# gen2down6basic.net
KiCad netlist of a schematic drawn in EAGLE
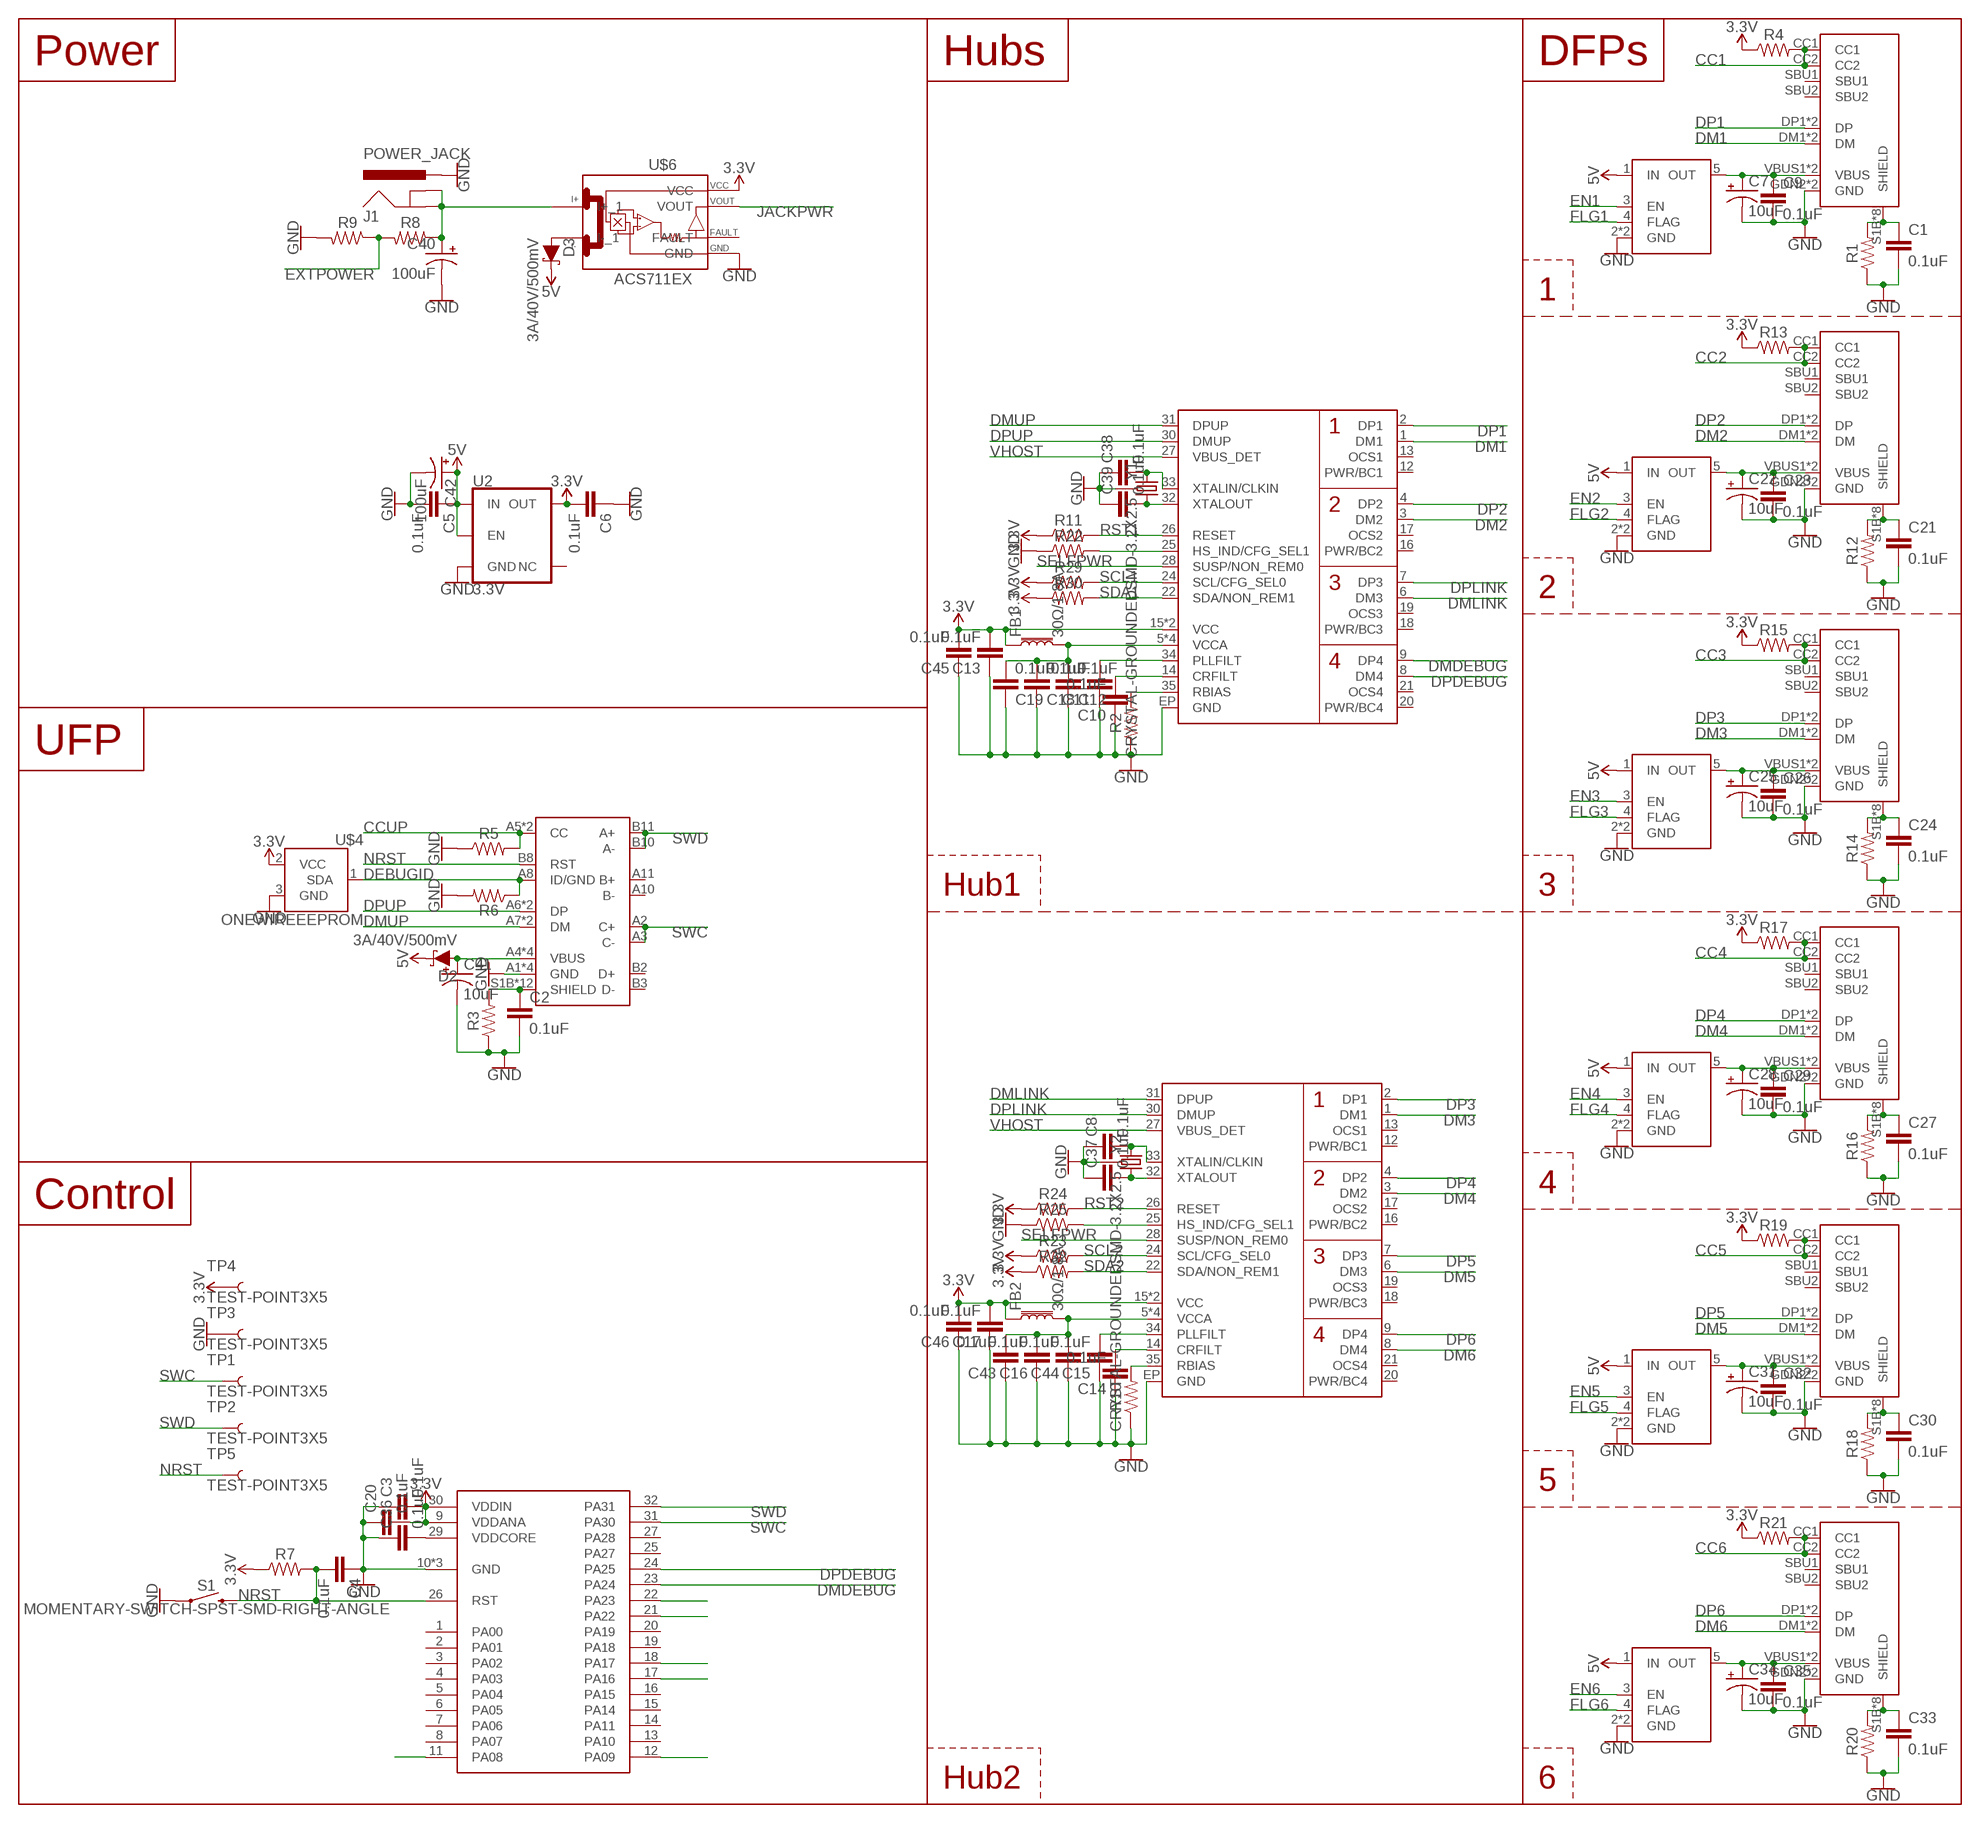
[diagram p0: schematic, sheet 1]

(export (version "E")
  (design (tool "Eeschema 10.0.6"))
  (components
    (comp (ref "C1")
      (value "0.1uF")
      (footprint "eagle-import:0603")
      (libsource (lib "eagle-import") (part "0.1UF-0603-25V-(+80/-20%)"))
    )
    (comp (ref "C2")
      (value "0.1uF")
      (footprint "eagle-import:0603")
      (libsource (lib "eagle-import") (part "0.1UF-0603-25V-(+80/-20%)"))
    )
    (comp (ref "C3")
      (value "0.1uF")
      (footprint "eagle-import:0603")
      (libsource (lib "eagle-import") (part "0.1UF-0603-25V-(+80/-20%)"))
    )
    (comp (ref "C4")
      (value "0.1uF")
      (footprint "eagle-import:0603")
      (libsource (lib "eagle-import") (part "0.1UF-0603-25V-(+80/-20%)"))
    )
    (comp (ref "C5")
      (value "0.1uF")
      (footprint "eagle-import:0603")
      (libsource (lib "eagle-import") (part "0.1UF-0603-25V-(+80/-20%)"))
    )
    (comp (ref "C6")
      (value "0.1uF")
      (footprint "eagle-import:0603")
      (libsource (lib "eagle-import") (part "0.1UF-0603-25V-(+80/-20%)"))
    )
    (comp (ref "C7")
      (value "10uF")
      (footprint "eagle-import:CPOL-RADIAL-2.5MM-5MM")
      (libsource (lib "eagle-import") (part "10UF-POLAR-RADIAL-2.5MM-25V-20%"))
    )
    (comp (ref "C8")
      (value "0.1uF")
      (footprint "eagle-import:0603")
      (libsource (lib "eagle-import") (part "0.1UF-0603-25V-(+80/-20%)"))
    )
    (comp (ref "C9")
      (value "0.1uF")
      (footprint "eagle-import:0603")
      (libsource (lib "eagle-import") (part "0.1UF-0603-25V-(+80/-20%)"))
    )
    (comp (ref "C10")
      (value "0.1uF")
      (footprint "eagle-import:0603")
      (libsource (lib "eagle-import") (part "0.1UF-0603-25V-(+80/-20%)"))
    )
    (comp (ref "C11")
      (value "0.1uF")
      (footprint "eagle-import:0603")
      (libsource (lib "eagle-import") (part "0.1UF-0603-25V-(+80/-20%)"))
    )
    (comp (ref "C12")
      (value "0.1uF")
      (footprint "eagle-import:0603")
      (libsource (lib "eagle-import") (part "0.1UF-0603-25V-(+80/-20%)"))
    )
    (comp (ref "C13")
      (value "0.1uF")
      (footprint "eagle-import:0603")
      (libsource (lib "eagle-import") (part "0.1UF-0603-25V-(+80/-20%)"))
    )
    (comp (ref "C14")
      (value "0.1uF")
      (footprint "eagle-import:0603")
      (libsource (lib "eagle-import") (part "0.1UF-0603-25V-(+80/-20%)"))
    )
    (comp (ref "C15")
      (value "0.1uF")
      (footprint "eagle-import:0603")
      (libsource (lib "eagle-import") (part "0.1UF-0603-25V-(+80/-20%)"))
    )
    (comp (ref "C16")
      (value "0.1uF")
      (footprint "eagle-import:0603")
      (libsource (lib "eagle-import") (part "0.1UF-0603-25V-(+80/-20%)"))
    )
    (comp (ref "C17")
      (value "0.1uF")
      (footprint "eagle-import:0603")
      (libsource (lib "eagle-import") (part "0.1UF-0603-25V-(+80/-20%)"))
    )
    (comp (ref "C18")
      (value "0.1uF")
      (footprint "eagle-import:0603")
      (libsource (lib "eagle-import") (part "0.1UF-0603-25V-(+80/-20%)"))
    )
    (comp (ref "C19")
      (value "0.1uF")
      (footprint "eagle-import:0603")
      (libsource (lib "eagle-import") (part "0.1UF-0603-25V-(+80/-20%)"))
    )
    (comp (ref "C20")
      (value "0.1uF")
      (footprint "eagle-import:0603")
      (libsource (lib "eagle-import") (part "0.1UF-0603-25V-(+80/-20%)"))
    )
    (comp (ref "C21")
      (value "0.1uF")
      (footprint "eagle-import:0603")
      (libsource (lib "eagle-import") (part "0.1UF-0603-25V-(+80/-20%)"))
    )
    (comp (ref "C22")
      (value "10uF")
      (footprint "eagle-import:CPOL-RADIAL-2.5MM-5MM")
      (libsource (lib "eagle-import") (part "10UF-POLAR-RADIAL-2.5MM-25V-20%"))
    )
    (comp (ref "C23")
      (value "0.1uF")
      (footprint "eagle-import:0603")
      (libsource (lib "eagle-import") (part "0.1UF-0603-25V-(+80/-20%)"))
    )
    (comp (ref "C24")
      (value "0.1uF")
      (footprint "eagle-import:0603")
      (libsource (lib "eagle-import") (part "0.1UF-0603-25V-(+80/-20%)"))
    )
    (comp (ref "C25")
      (value "10uF")
      (footprint "eagle-import:CPOL-RADIAL-2.5MM-5MM")
      (libsource (lib "eagle-import") (part "10UF-POLAR-RADIAL-2.5MM-25V-20%"))
    )
    (comp (ref "C26")
      (value "0.1uF")
      (footprint "eagle-import:0603")
      (libsource (lib "eagle-import") (part "0.1UF-0603-25V-(+80/-20%)"))
    )
    (comp (ref "C27")
      (value "0.1uF")
      (footprint "eagle-import:0603")
      (libsource (lib "eagle-import") (part "0.1UF-0603-25V-(+80/-20%)"))
    )
    (comp (ref "C28")
      (value "10uF")
      (footprint "eagle-import:CPOL-RADIAL-2.5MM-5MM")
      (libsource (lib "eagle-import") (part "10UF-POLAR-RADIAL-2.5MM-25V-20%"))
    )
    (comp (ref "C29")
      (value "0.1uF")
      (footprint "eagle-import:0603")
      (libsource (lib "eagle-import") (part "0.1UF-0603-25V-(+80/-20%)"))
    )
    (comp (ref "C30")
      (value "0.1uF")
      (footprint "eagle-import:0603")
      (libsource (lib "eagle-import") (part "0.1UF-0603-25V-(+80/-20%)"))
    )
    (comp (ref "C31")
      (value "10uF")
      (footprint "eagle-import:CPOL-RADIAL-2.5MM-5MM")
      (libsource (lib "eagle-import") (part "10UF-POLAR-RADIAL-2.5MM-25V-20%"))
    )
    (comp (ref "C32")
      (value "0.1uF")
      (footprint "eagle-import:0603")
      (libsource (lib "eagle-import") (part "0.1UF-0603-25V-(+80/-20%)"))
    )
    (comp (ref "C33")
      (value "0.1uF")
      (footprint "eagle-import:0603")
      (libsource (lib "eagle-import") (part "0.1UF-0603-25V-(+80/-20%)"))
    )
    (comp (ref "C34")
      (value "10uF")
      (footprint "eagle-import:CPOL-RADIAL-2.5MM-5MM")
      (libsource (lib "eagle-import") (part "10UF-POLAR-RADIAL-2.5MM-25V-20%"))
    )
    (comp (ref "C35")
      (value "0.1uF")
      (footprint "eagle-import:0603")
      (libsource (lib "eagle-import") (part "0.1UF-0603-25V-(+80/-20%)"))
    )
    (comp (ref "C36")
      (value "0.1uF")
      (footprint "eagle-import:0603")
      (libsource (lib "eagle-import") (part "0.1UF-0603-25V-(+80/-20%)"))
    )
    (comp (ref "C37")
      (value "0.1uF")
      (footprint "eagle-import:0603")
      (libsource (lib "eagle-import") (part "0.1UF-0603-25V-(+80/-20%)"))
    )
    (comp (ref "C38")
      (value "0.1uF")
      (footprint "eagle-import:0603")
      (libsource (lib "eagle-import") (part "0.1UF-0603-25V-(+80/-20%)"))
    )
    (comp (ref "C39")
      (value "0.1uF")
      (footprint "eagle-import:0603")
      (libsource (lib "eagle-import") (part "0.1UF-0603-25V-(+80/-20%)"))
    )
    (comp (ref "C40")
      (value "100uF")
      (footprint "eagle-import:CPOL-RADIAL-2.5MM-6.5MM")
      (libsource (lib "eagle-import") (part "100UF-POLAR-RADIAL-2.5MM-25V-20%"))
    )
    (comp (ref "C41")
      (value "10uF")
      (footprint "eagle-import:CPOL-RADIAL-2.5MM-5MM")
      (libsource (lib "eagle-import") (part "10UF-POLAR-RADIAL-2.5MM-25V-20%"))
    )
    (comp (ref "C42")
      (value "100uF")
      (footprint "eagle-import:CPOL-RADIAL-2.5MM-6.5MM")
      (libsource (lib "eagle-import") (part "100UF-POLAR-RADIAL-2.5MM-25V-20%"))
    )
    (comp (ref "C43")
      (value "0.1uF")
      (footprint "eagle-import:0603")
      (libsource (lib "eagle-import") (part "0.1UF-0603-25V-(+80/-20%)"))
    )
    (comp (ref "C44")
      (value "0.1uF")
      (footprint "eagle-import:0603")
      (libsource (lib "eagle-import") (part "0.1UF-0603-25V-(+80/-20%)"))
    )
    (comp (ref "C45")
      (value "0.1uF")
      (footprint "eagle-import:0603")
      (libsource (lib "eagle-import") (part "0.1UF-0603-25V-(+80/-20%)"))
    )
    (comp (ref "C46")
      (value "0.1uF")
      (footprint "eagle-import:0603")
      (libsource (lib "eagle-import") (part "0.1UF-0603-25V-(+80/-20%)"))
    )
    (comp (ref "D2")
      (value "3A/40V/500mV")
      (footprint "eagle-import:SMA-DIODE")
      (libsource (lib "eagle-import") (part "DIODE-SCHOTTKY-B340A"))
    )
    (comp (ref "D3")
      (value "3A/40V/500mV")
      (footprint "eagle-import:SMA-DIODE")
      (libsource (lib "eagle-import") (part "DIODE-SCHOTTKY-B340A"))
    )
    (comp (ref "FB1")
      (value "30Ω/1.8A")
      (footprint "eagle-import:0603")
      (libsource (lib "eagle-import") (part "FERRITE_BEAD-0603"))
    )
    (comp (ref "FB2")
      (value "30Ω/1.8A")
      (footprint "eagle-import:0603")
      (libsource (lib "eagle-import") (part "FERRITE_BEAD-0603"))
    )
    (comp (ref "J1")
      (value "POWER_JACK")
      (footprint "eagle-import:POWER_JACK_PTH")
      (libsource (lib "eagle-import") (part "POWER_JACK"))
    )
    (comp (ref "R1")
      (value "RESISTOR0603")
      (footprint "eagle-import:0603")
      (libsource (lib "eagle-import") (part "RESISTOR0603"))
    )
    (comp (ref "R2")
      (value "RESISTOR0603")
      (footprint "eagle-import:0603")
      (libsource (lib "eagle-import") (part "RESISTOR0603"))
    )
    (comp (ref "R3")
      (value "RESISTOR0603")
      (footprint "eagle-import:0603")
      (libsource (lib "eagle-import") (part "RESISTOR0603"))
    )
    (comp (ref "R4")
      (value "RESISTOR0603")
      (footprint "eagle-import:0603")
      (libsource (lib "eagle-import") (part "RESISTOR0603"))
    )
    (comp (ref "R5")
      (value "RESISTOR0603")
      (footprint "eagle-import:0603")
      (libsource (lib "eagle-import") (part "RESISTOR0603"))
    )
    (comp (ref "R6")
      (value "RESISTOR0603")
      (footprint "eagle-import:0603")
      (libsource (lib "eagle-import") (part "RESISTOR0603"))
    )
    (comp (ref "R7")
      (value "RESISTOR0603")
      (footprint "eagle-import:0603")
      (libsource (lib "eagle-import") (part "RESISTOR0603"))
    )
    (comp (ref "R8")
      (value "RESISTOR0603")
      (footprint "eagle-import:0603")
      (libsource (lib "eagle-import") (part "RESISTOR0603"))
    )
    (comp (ref "R9")
      (value "RESISTOR0603")
      (footprint "eagle-import:0603")
      (libsource (lib "eagle-import") (part "RESISTOR0603"))
    )
    (comp (ref "R10")
      (value "RESISTOR0603")
      (footprint "eagle-import:0603")
      (libsource (lib "eagle-import") (part "RESISTOR0603"))
    )
    (comp (ref "R11")
      (value "RESISTOR0603")
      (footprint "eagle-import:0603")
      (libsource (lib "eagle-import") (part "RESISTOR0603"))
    )
    (comp (ref "R12")
      (value "RESISTOR0603")
      (footprint "eagle-import:0603")
      (libsource (lib "eagle-import") (part "RESISTOR0603"))
    )
    (comp (ref "R13")
      (value "RESISTOR0603")
      (footprint "eagle-import:0603")
      (libsource (lib "eagle-import") (part "RESISTOR0603"))
    )
    (comp (ref "R14")
      (value "RESISTOR0603")
      (footprint "eagle-import:0603")
      (libsource (lib "eagle-import") (part "RESISTOR0603"))
    )
    (comp (ref "R15")
      (value "RESISTOR0603")
      (footprint "eagle-import:0603")
      (libsource (lib "eagle-import") (part "RESISTOR0603"))
    )
    (comp (ref "R16")
      (value "RESISTOR0603")
      (footprint "eagle-import:0603")
      (libsource (lib "eagle-import") (part "RESISTOR0603"))
    )
    (comp (ref "R17")
      (value "RESISTOR0603")
      (footprint "eagle-import:0603")
      (libsource (lib "eagle-import") (part "RESISTOR0603"))
    )
    (comp (ref "R18")
      (value "RESISTOR0603")
      (footprint "eagle-import:0603")
      (libsource (lib "eagle-import") (part "RESISTOR0603"))
    )
    (comp (ref "R19")
      (value "RESISTOR0603")
      (footprint "eagle-import:0603")
      (libsource (lib "eagle-import") (part "RESISTOR0603"))
    )
    (comp (ref "R20")
      (value "RESISTOR0603")
      (footprint "eagle-import:0603")
      (libsource (lib "eagle-import") (part "RESISTOR0603"))
    )
    (comp (ref "R21")
      (value "RESISTOR0603")
      (footprint "eagle-import:0603")
      (libsource (lib "eagle-import") (part "RESISTOR0603"))
    )
    (comp (ref "R22")
      (value "RESISTOR0603")
      (footprint "eagle-import:0603")
      (libsource (lib "eagle-import") (part "RESISTOR0603"))
    )
    (comp (ref "R23")
      (value "RESISTOR0603")
      (footprint "eagle-import:0603")
      (libsource (lib "eagle-import") (part "RESISTOR0603"))
    )
    (comp (ref "R24")
      (value "RESISTOR0603")
      (footprint "eagle-import:0603")
      (libsource (lib "eagle-import") (part "RESISTOR0603"))
    )
    (comp (ref "R25")
      (value "RESISTOR0603")
      (footprint "eagle-import:0603")
      (libsource (lib "eagle-import") (part "RESISTOR0603"))
    )
    (comp (ref "R29")
      (value "RESISTOR0603")
      (footprint "eagle-import:0603")
      (libsource (lib "eagle-import") (part "RESISTOR0603"))
    )
    (comp (ref "R30")
      (value "RESISTOR0603")
      (footprint "eagle-import:0603")
      (libsource (lib "eagle-import") (part "RESISTOR0603"))
    )
    (comp (ref "R32")
      (value "RESISTOR0603")
      (footprint "eagle-import:0603")
      (libsource (lib "eagle-import") (part "RESISTOR0603"))
    )
    (comp (ref "S1")
      (value "MOMENTARY-SWITCH-SPST-SMD-RIGHT-ANGLE")
      (footprint "eagle-import:TACTILE_SWITCH_SMD_RIGHT_ANGLE")
      (libsource (lib "eagle-import") (part "MOMENTARY-SWITCH-SPST-SMD-RIGHT-ANGLE"))
    )
    (comp (ref "TP1")
      (value "TEST-POINT3X5")
      (footprint "eagle-import:PAD.03X.05")
      (libsource (lib "eagle-import") (part "TEST-POINT3X5"))
    )
    (comp (ref "TP2")
      (value "TEST-POINT3X5")
      (footprint "eagle-import:PAD.03X.05")
      (libsource (lib "eagle-import") (part "TEST-POINT3X5"))
    )
    (comp (ref "TP3")
      (value "TEST-POINT3X5")
      (footprint "eagle-import:PAD.03X.05")
      (libsource (lib "eagle-import") (part "TEST-POINT3X5"))
    )
    (comp (ref "TP4")
      (value "TEST-POINT3X5")
      (footprint "eagle-import:PAD.03X.05")
      (libsource (lib "eagle-import") (part "TEST-POINT3X5"))
    )
    (comp (ref "TP5")
      (value "TEST-POINT3X5")
      (footprint "eagle-import:PAD.03X.05")
      (libsource (lib "eagle-import") (part "TEST-POINT3X5"))
    )
    (comp (ref "U$1")
      (value "AP22804/14*SN")
      (footprint "eagle-import:UDFN2020-6-EP")
      (libsource (lib "eagle-import") (part "AP22804/14SN"))
    )
    (comp (ref "U$2")
      (value "USB-C_DEBUG-HORZ-F")
      (footprint "eagle-import:USB-C_24PIN_HORZ-F-UNTESTED")
      (libsource (lib "eagle-import") (part "USB-C_DEBUG-HORZ-F"))
    )
    (comp (ref "U$3")
      (value "USB-C_USB2ONLY-HORZ-F_12P")
      (footprint "eagle-import:USB-C_12PIN_HORZ-F")
      (libsource (lib "eagle-import") (part "USB-C_USB2ONLY-HORZ-F_12P"))
    )
    (comp (ref "U$4")
      (value "ONEWIREEEPROM")
      (footprint "eagle-import:SOT23-3")
      (libsource (lib "eagle-import") (part "ONEWIREEEPROM"))
    )
    (comp (ref "U$5")
      (value "USB2512/3/4")
      (footprint "eagle-import:QFN36_6X6")
      (libsource (lib "eagle-import") (part "USB2512/3/4"))
    )
    (comp (ref "U$6")
      (value "ACS711EX")
      (footprint "eagle-import:QFN12_3X3-CURRENT")
      (libsource (lib "eagle-import") (part "ACS711EX"))
    )
    (comp (ref "U$7")
      (value "USB2512/3/4")
      (footprint "eagle-import:QFN36_6X6")
      (libsource (lib "eagle-import") (part "USB2512/3/4"))
    )
    (comp (ref "U$8")
      (value "ATSAMD2E1A-M")
      (footprint "eagle-import:QFN32_5X5")
      (libsource (lib "eagle-import") (part "ATSAMD2E1A-M"))
    )
    (comp (ref "U$10")
      (value "USB-C_USB2ONLY-HORZ-F_12P")
      (footprint "eagle-import:USB-C_12PIN_HORZ-F")
      (libsource (lib "eagle-import") (part "USB-C_USB2ONLY-HORZ-F_12P"))
    )
    (comp (ref "U$11")
      (value "AP22804/14*SN")
      (footprint "eagle-import:UDFN2020-6-EP")
      (libsource (lib "eagle-import") (part "AP22804/14SN"))
    )
    (comp (ref "U$12")
      (value "USB-C_USB2ONLY-HORZ-F_12P")
      (footprint "eagle-import:USB-C_12PIN_HORZ-F")
      (libsource (lib "eagle-import") (part "USB-C_USB2ONLY-HORZ-F_12P"))
    )
    (comp (ref "U$13")
      (value "AP22804/14*SN")
      (footprint "eagle-import:UDFN2020-6-EP")
      (libsource (lib "eagle-import") (part "AP22804/14SN"))
    )
    (comp (ref "U$14")
      (value "USB-C_USB2ONLY-HORZ-F_12P")
      (footprint "eagle-import:USB-C_12PIN_HORZ-F")
      (libsource (lib "eagle-import") (part "USB-C_USB2ONLY-HORZ-F_12P"))
    )
    (comp (ref "U$15")
      (value "AP22804/14*SN")
      (footprint "eagle-import:UDFN2020-6-EP")
      (libsource (lib "eagle-import") (part "AP22804/14SN"))
    )
    (comp (ref "U$16")
      (value "USB-C_USB2ONLY-HORZ-F_12P")
      (footprint "eagle-import:USB-C_12PIN_HORZ-F")
      (libsource (lib "eagle-import") (part "USB-C_USB2ONLY-HORZ-F_12P"))
    )
    (comp (ref "U$17")
      (value "AP22804/14*SN")
      (footprint "eagle-import:UDFN2020-6-EP")
      (libsource (lib "eagle-import") (part "AP22804/14SN"))
    )
    (comp (ref "U$18")
      (value "USB-C_USB2ONLY-HORZ-F_12P")
      (footprint "eagle-import:USB-C_12PIN_HORZ-F")
      (libsource (lib "eagle-import") (part "USB-C_USB2ONLY-HORZ-F_12P"))
    )
    (comp (ref "U$19")
      (value "AP22804/14*SN")
      (footprint "eagle-import:UDFN2020-6-EP")
      (libsource (lib "eagle-import") (part "AP22804/14SN"))
    )
    (comp (ref "U2")
      (value "3.3V")
      (footprint "eagle-import:SOT23-5")
      (libsource (lib "eagle-import") (part "V_REG_AP2112K-3.3V"))
    )
    (comp (ref "Y1")
      (value "CRYSTAL-GROUNDEDSMD-3.2X2.5")
      (footprint "eagle-import:CRYSTAL-SMD-3.2X2.5MM")
      (libsource (lib "eagle-import") (part "CRYSTAL-GROUNDEDSMD-3.2X2.5"))
    )
    (comp (ref "Y2")
      (value "CRYSTAL-GROUNDEDSMD-3.2X2.5")
      (footprint "eagle-import:CRYSTAL-SMD-3.2X2.5MM")
      (libsource (lib "eagle-import") (part "CRYSTAL-GROUNDEDSMD-3.2X2.5"))
    )
  )
  (nets
    (net (code "1") (name "/CC1") (class "Default")
      (node (ref "R4") (pin "2") (pinfunction "2_2") (pintype "passive"))
      (node (ref "U$3") (pin "CC1") (pinfunction "CC1_CC1") (pintype "bidirectional"))
      (node (ref "U$3") (pin "CC2") (pinfunction "CC2_CC2") (pintype "bidirectional"))
    )
    (net (code "2") (name "/CC2") (class "Default")
      (node (ref "R13") (pin "2") (pinfunction "2_2") (pintype "passive"))
      (node (ref "U$10") (pin "CC1") (pinfunction "CC1_CC1") (pintype "bidirectional"))
      (node (ref "U$10") (pin "CC2") (pinfunction "CC2_CC2") (pintype "bidirectional"))
    )
    (net (code "3") (name "/CC3") (class "Default")
      (node (ref "R15") (pin "2") (pinfunction "2_2") (pintype "passive"))
      (node (ref "U$12") (pin "CC1") (pinfunction "CC1_CC1") (pintype "bidirectional"))
      (node (ref "U$12") (pin "CC2") (pinfunction "CC2_CC2") (pintype "bidirectional"))
    )
    (net (code "4") (name "/CC4") (class "Default")
      (node (ref "R17") (pin "2") (pinfunction "2_2") (pintype "passive"))
      (node (ref "U$14") (pin "CC1") (pinfunction "CC1_CC1") (pintype "bidirectional"))
      (node (ref "U$14") (pin "CC2") (pinfunction "CC2_CC2") (pintype "bidirectional"))
    )
    (net (code "5") (name "/CC5") (class "Default")
      (node (ref "R19") (pin "2") (pinfunction "2_2") (pintype "passive"))
      (node (ref "U$16") (pin "CC1") (pinfunction "CC1_CC1") (pintype "bidirectional"))
      (node (ref "U$16") (pin "CC2") (pinfunction "CC2_CC2") (pintype "bidirectional"))
    )
    (net (code "6") (name "/CC6") (class "Default")
      (node (ref "R21") (pin "2") (pinfunction "2_2") (pintype "passive"))
      (node (ref "U$18") (pin "CC1") (pinfunction "CC1_CC1") (pintype "bidirectional"))
      (node (ref "U$18") (pin "CC2") (pinfunction "CC2_CC2") (pintype "bidirectional"))
    )
    (net (code "7") (name "/CCUP") (class "Default")
      (node (ref "R5") (pin "2") (pinfunction "2_2") (pintype "passive"))
      (node (ref "U$2") (pin "A5") (pinfunction "CC_A5") (pintype "bidirectional"))
      (node (ref "U$2") (pin "B5") (pinfunction "CC_B5") (pintype "bidirectional"))
    )
    (net (code "8") (name "/DEBUGID") (class "Default")
      (node (ref "R6") (pin "1") (pinfunction "1_1") (pintype "passive"))
      (node (ref "U$2") (pin "A8") (pinfunction "ID/GND_A8") (pintype "bidirectional"))
      (node (ref "U$4") (pin "1") (pinfunction "SDA_1") (pintype "bidirectional"))
    )
    (net (code "9") (name "/DM1") (class "Default")
      (node (ref "U$3") (pin "DM1") (pinfunction "DM_DM1") (pintype "bidirectional"))
      (node (ref "U$3") (pin "DM2") (pinfunction "DM_DM2") (pintype "bidirectional"))
      (node (ref "U$5") (pin "1") (pinfunction "DM1_1") (pintype "bidirectional"))
    )
    (net (code "10") (name "/DM2") (class "Default")
      (node (ref "U$10") (pin "DM1") (pinfunction "DM_DM1") (pintype "bidirectional"))
      (node (ref "U$10") (pin "DM2") (pinfunction "DM_DM2") (pintype "bidirectional"))
      (node (ref "U$5") (pin "3") (pinfunction "DM2_3") (pintype "bidirectional"))
    )
    (net (code "11") (name "/DM3") (class "Default")
      (node (ref "U$12") (pin "DM1") (pinfunction "DM_DM1") (pintype "bidirectional"))
      (node (ref "U$12") (pin "DM2") (pinfunction "DM_DM2") (pintype "bidirectional"))
      (node (ref "U$7") (pin "1") (pinfunction "DM1_1") (pintype "bidirectional"))
    )
    (net (code "12") (name "/DM4") (class "Default")
      (node (ref "U$14") (pin "DM1") (pinfunction "DM_DM1") (pintype "bidirectional"))
      (node (ref "U$14") (pin "DM2") (pinfunction "DM_DM2") (pintype "bidirectional"))
      (node (ref "U$7") (pin "3") (pinfunction "DM2_3") (pintype "bidirectional"))
    )
    (net (code "13") (name "/DM5") (class "Default")
      (node (ref "U$16") (pin "DM1") (pinfunction "DM_DM1") (pintype "bidirectional"))
      (node (ref "U$16") (pin "DM2") (pinfunction "DM_DM2") (pintype "bidirectional"))
      (node (ref "U$7") (pin "6") (pinfunction "DM3_6") (pintype "bidirectional"))
    )
    (net (code "14") (name "/DM6") (class "Default")
      (node (ref "U$18") (pin "DM1") (pinfunction "DM_DM1") (pintype "bidirectional"))
      (node (ref "U$18") (pin "DM2") (pinfunction "DM_DM2") (pintype "bidirectional"))
      (node (ref "U$7") (pin "8") (pinfunction "DM4_8") (pintype "bidirectional"))
    )
    (net (code "15") (name "/DMDEBUG") (class "Default")
      (node (ref "U$5") (pin "9") (pinfunction "DP4_9") (pintype "bidirectional"))
      (node (ref "U$8") (pin "23") (pinfunction "PA24_23") (pintype "bidirectional"))
    )
    (net (code "16") (name "/DMLINK") (class "Default")
      (node (ref "U$5") (pin "6") (pinfunction "DM3_6") (pintype "bidirectional"))
      (node (ref "U$7") (pin "31") (pinfunction "DPUP_31") (pintype "bidirectional"))
    )
    (net (code "17") (name "/DMUP") (class "Default")
      (node (ref "U$2") (pin "A7") (pinfunction "DM_A7") (pintype "bidirectional"))
      (node (ref "U$2") (pin "B7") (pinfunction "DM_B7") (pintype "bidirectional"))
      (node (ref "U$5") (pin "31") (pinfunction "DPUP_31") (pintype "bidirectional"))
    )
    (net (code "18") (name "/DP1") (class "Default")
      (node (ref "U$3") (pin "DP1") (pinfunction "DP_DP1") (pintype "bidirectional"))
      (node (ref "U$3") (pin "DP2") (pinfunction "DP_DP2") (pintype "bidirectional"))
      (node (ref "U$5") (pin "2") (pinfunction "DP1_2") (pintype "bidirectional"))
    )
    (net (code "19") (name "/DP2") (class "Default")
      (node (ref "U$10") (pin "DP1") (pinfunction "DP_DP1") (pintype "bidirectional"))
      (node (ref "U$10") (pin "DP2") (pinfunction "DP_DP2") (pintype "bidirectional"))
      (node (ref "U$5") (pin "4") (pinfunction "DP2_4") (pintype "bidirectional"))
    )
    (net (code "20") (name "/DP3") (class "Default")
      (node (ref "U$12") (pin "DP1") (pinfunction "DP_DP1") (pintype "bidirectional"))
      (node (ref "U$12") (pin "DP2") (pinfunction "DP_DP2") (pintype "bidirectional"))
      (node (ref "U$7") (pin "2") (pinfunction "DP1_2") (pintype "bidirectional"))
    )
    (net (code "21") (name "/DP4") (class "Default")
      (node (ref "U$14") (pin "DP1") (pinfunction "DP_DP1") (pintype "bidirectional"))
      (node (ref "U$14") (pin "DP2") (pinfunction "DP_DP2") (pintype "bidirectional"))
      (node (ref "U$7") (pin "4") (pinfunction "DP2_4") (pintype "bidirectional"))
    )
    (net (code "22") (name "/DP5") (class "Default")
      (node (ref "U$16") (pin "DP1") (pinfunction "DP_DP1") (pintype "bidirectional"))
      (node (ref "U$16") (pin "DP2") (pinfunction "DP_DP2") (pintype "bidirectional"))
      (node (ref "U$7") (pin "7") (pinfunction "DP3_7") (pintype "bidirectional"))
    )
    (net (code "23") (name "/DP6") (class "Default")
      (node (ref "U$18") (pin "DP1") (pinfunction "DP_DP1") (pintype "bidirectional"))
      (node (ref "U$18") (pin "DP2") (pinfunction "DP_DP2") (pintype "bidirectional"))
      (node (ref "U$7") (pin "9") (pinfunction "DP4_9") (pintype "bidirectional"))
    )
    (net (code "24") (name "/DPDEBUG") (class "Default")
      (node (ref "U$5") (pin "8") (pinfunction "DM4_8") (pintype "bidirectional"))
      (node (ref "U$8") (pin "24") (pinfunction "PA25_24") (pintype "bidirectional"))
    )
    (net (code "25") (name "/DPLINK") (class "Default")
      (node (ref "U$5") (pin "7") (pinfunction "DP3_7") (pintype "bidirectional"))
      (node (ref "U$7") (pin "30") (pinfunction "DMUP_30") (pintype "bidirectional"))
    )
    (net (code "26") (name "/DPUP") (class "Default")
      (node (ref "U$2") (pin "A6") (pinfunction "DP_A6") (pintype "bidirectional"))
      (node (ref "U$2") (pin "B6") (pinfunction "DP_B6") (pintype "bidirectional"))
      (node (ref "U$5") (pin "30") (pinfunction "DMUP_30") (pintype "bidirectional"))
    )
    (net (code "27") (name "/EN1") (class "Default")
      (node (ref "U$1") (pin "3") (pinfunction "EN_3") (pintype "bidirectional"))
    )
    (net (code "28") (name "/EN2") (class "Default")
      (node (ref "U$11") (pin "3") (pinfunction "EN_3") (pintype "bidirectional"))
    )
    (net (code "29") (name "/EN3") (class "Default")
      (node (ref "U$13") (pin "3") (pinfunction "EN_3") (pintype "bidirectional"))
    )
    (net (code "30") (name "/EN4") (class "Default")
      (node (ref "U$15") (pin "3") (pinfunction "EN_3") (pintype "bidirectional"))
    )
    (net (code "31") (name "/EN5") (class "Default")
      (node (ref "U$17") (pin "3") (pinfunction "EN_3") (pintype "bidirectional"))
    )
    (net (code "32") (name "/EN6") (class "Default")
      (node (ref "U$19") (pin "3") (pinfunction "EN_3") (pintype "bidirectional"))
    )
    (net (code "33") (name "/EXTPOWER") (class "Default")
      (node (ref "R8") (pin "2") (pinfunction "2_2") (pintype "passive"))
      (node (ref "R9") (pin "1") (pinfunction "1_1") (pintype "passive"))
    )
    (net (code "34") (name "/FLG1") (class "Default")
      (node (ref "U$1") (pin "4") (pinfunction "FLAG_4") (pintype "bidirectional"))
    )
    (net (code "35") (name "/FLG2") (class "Default")
      (node (ref "U$11") (pin "4") (pinfunction "FLAG_4") (pintype "bidirectional"))
    )
    (net (code "36") (name "/FLG3") (class "Default")
      (node (ref "U$13") (pin "4") (pinfunction "FLAG_4") (pintype "bidirectional"))
    )
    (net (code "37") (name "/FLG4") (class "Default")
      (node (ref "U$15") (pin "4") (pinfunction "FLAG_4") (pintype "bidirectional"))
    )
    (net (code "38") (name "/FLG5") (class "Default")
      (node (ref "U$17") (pin "4") (pinfunction "FLAG_4") (pintype "bidirectional"))
    )
    (net (code "39") (name "/FLG6") (class "Default")
      (node (ref "U$19") (pin "4") (pinfunction "FLAG_4") (pintype "bidirectional"))
    )
    (net (code "40") (name "/JACKPWR") (class "Default")
      (node (ref "U$6") (pin "P$9") (pinfunction "VOUT_P$9") (pintype "output"))
    )
    (net (code "41") (name "/NRST") (class "Default")
      (node (ref "C4") (pin "2") (pinfunction "2_2") (pintype "passive"))
      (node (ref "R7") (pin "2") (pinfunction "2_2") (pintype "passive"))
      (node (ref "S1") (pin "2") (pinfunction "2_2") (pintype "passive"))
      (node (ref "TP5") (pin "P$1") (pinfunction "1_P$1") (pintype "bidirectional"))
      (node (ref "U$2") (pin "B8") (pinfunction "RST_B8") (pintype "bidirectional"))
      (node (ref "U$8") (pin "26") (pinfunction "RST_26") (pintype "bidirectional"))
    )
    (net (code "42") (name "/RST1") (class "Default")
      (node (ref "R11") (pin "2") (pinfunction "2_2") (pintype "passive"))
      (node (ref "U$5") (pin "26") (pinfunction "RESET_26") (pintype "bidirectional"))
    )
    (net (code "43") (name "/RST2") (class "Default")
      (node (ref "R24") (pin "2") (pinfunction "2_2") (pintype "passive"))
      (node (ref "U$7") (pin "26") (pinfunction "RESET_26") (pintype "bidirectional"))
    )
    (net (code "44") (name "/SCL1") (class "Default")
      (node (ref "R29") (pin "2") (pinfunction "2_2") (pintype "passive"))
      (node (ref "U$5") (pin "24") (pinfunction "SCL/CFG_SEL0_24") (pintype "bidirectional"))
    )
    (net (code "45") (name "/SCL2") (class "Default")
      (node (ref "R23") (pin "2") (pinfunction "2_2") (pintype "passive"))
      (node (ref "U$7") (pin "24") (pinfunction "SCL/CFG_SEL0_24") (pintype "bidirectional"))
    )
    (net (code "46") (name "/SDA1") (class "Default")
      (node (ref "R30") (pin "2") (pinfunction "2_2") (pintype "passive"))
      (node (ref "U$5") (pin "22") (pinfunction "SDA/NON_REM1_22") (pintype "bidirectional"))
    )
    (net (code "47") (name "/SDA2") (class "Default")
      (node (ref "R32") (pin "2") (pinfunction "2_2") (pintype "passive"))
      (node (ref "U$7") (pin "22") (pinfunction "SDA/NON_REM1_22") (pintype "bidirectional"))
    )
    (net (code "48") (name "/SELFPWR") (class "Default")
      (node (ref "U$5") (pin "28") (pinfunction "SUSP/NON_REM0_28") (pintype "bidirectional"))
      (node (ref "U$7") (pin "28") (pinfunction "SUSP/NON_REM0_28") (pintype "bidirectional"))
    )
    (net (code "49") (name "/SWC") (class "Default")
      (node (ref "TP1") (pin "P$1") (pinfunction "1_P$1") (pintype "bidirectional"))
      (node (ref "U$2") (pin "A2") (pinfunction "C+_A2") (pintype "bidirectional"))
      (node (ref "U$2") (pin "A3") (pinfunction "C-_A3") (pintype "bidirectional"))
      (node (ref "U$8") (pin "31") (pinfunction "PA30_31") (pintype "bidirectional"))
    )
    (net (code "50") (name "/SWD") (class "Default")
      (node (ref "TP2") (pin "P$1") (pinfunction "1_P$1") (pintype "bidirectional"))
      (node (ref "U$2") (pin "B10") (pinfunction "A-_B10") (pintype "bidirectional"))
      (node (ref "U$2") (pin "B11") (pinfunction "A+_B11") (pintype "bidirectional"))
      (node (ref "U$8") (pin "32") (pinfunction "PA31_32") (pintype "bidirectional"))
    )
    (net (code "51") (name "/VHOST") (class "Default")
      (node (ref "C41") (pin "1") (pinfunction "+_1") (pintype "passive"))
      (node (ref "D2") (pin "A") (pinfunction "A_A") (pintype "passive"))
      (node (ref "U$2") (pin "A4") (pinfunction "VBUS_A4") (pintype "bidirectional"))
      (node (ref "U$2") (pin "A9") (pinfunction "VBUS_A9") (pintype "bidirectional"))
      (node (ref "U$2") (pin "B4") (pinfunction "VBUS_B4") (pintype "bidirectional"))
      (node (ref "U$2") (pin "B9") (pinfunction "VBUS_B9") (pintype "bidirectional"))
      (node (ref "U$5") (pin "27") (pinfunction "VBUS_DET_27") (pintype "bidirectional"))
      (node (ref "U$7") (pin "27") (pinfunction "VBUS_DET_27") (pintype "bidirectional"))
    )
    (net (code "52") (name "3.3V") (class "Default")
      (node (ref "C13") (pin "2") (pinfunction "2_2") (pintype "passive"))
      (node (ref "C17") (pin "2") (pinfunction "2_2") (pintype "passive"))
      (node (ref "C20") (pin "2") (pinfunction "2_2") (pintype "passive"))
      (node (ref "C3") (pin "2") (pinfunction "2_2") (pintype "passive"))
      (node (ref "C45") (pin "2") (pinfunction "2_2") (pintype "passive"))
      (node (ref "C46") (pin "2") (pinfunction "2_2") (pintype "passive"))
      (node (ref "C6") (pin "2") (pinfunction "2_2") (pintype "passive"))
      (node (ref "FB1") (pin "1") (pinfunction "1_1") (pintype "passive"))
      (node (ref "FB2") (pin "1") (pinfunction "1_1") (pintype "passive"))
      (node (ref "R11") (pin "1") (pinfunction "1_1") (pintype "passive"))
      (node (ref "R13") (pin "1") (pinfunction "1_1") (pintype "passive"))
      (node (ref "R15") (pin "1") (pinfunction "1_1") (pintype "passive"))
      (node (ref "R17") (pin "1") (pinfunction "1_1") (pintype "passive"))
      (node (ref "R19") (pin "1") (pinfunction "1_1") (pintype "passive"))
      (node (ref "R21") (pin "1") (pinfunction "1_1") (pintype "passive"))
      (node (ref "R23") (pin "1") (pinfunction "1_1") (pintype "passive"))
      (node (ref "R24") (pin "1") (pinfunction "1_1") (pintype "passive"))
      (node (ref "R29") (pin "1") (pinfunction "1_1") (pintype "passive"))
      (node (ref "R30") (pin "1") (pinfunction "1_1") (pintype "passive"))
      (node (ref "R32") (pin "1") (pinfunction "1_1") (pintype "passive"))
      (node (ref "R4") (pin "1") (pinfunction "1_1") (pintype "passive"))
      (node (ref "R7") (pin "1") (pinfunction "1_1") (pintype "passive"))
      (node (ref "TP4") (pin "P$1") (pinfunction "1_P$1") (pintype "bidirectional"))
      (node (ref "U$4") (pin "2") (pinfunction "VCC_2") (pintype "bidirectional"))
      (node (ref "U$5") (pin "15") (pinfunction "VCC_15") (pintype "bidirectional"))
      (node (ref "U$5") (pin "23") (pinfunction "VCC_23") (pintype "bidirectional"))
      (node (ref "U$6") (pin "P$10") (pinfunction "VCC_P$10") (pintype "power_in"))
      (node (ref "U$7") (pin "15") (pinfunction "VCC_15") (pintype "bidirectional"))
      (node (ref "U$7") (pin "23") (pinfunction "VCC_23") (pintype "bidirectional"))
      (node (ref "U$8") (pin "30") (pinfunction "VDDIN_30") (pintype "bidirectional"))
      (node (ref "U$8") (pin "9") (pinfunction "VDDANA_9") (pintype "bidirectional"))
      (node (ref "U2") (pin "5") (pinfunction "OUT_5") (pintype "passive"))
    )
    (net (code "53") (name "5V") (class "Default")
      (node (ref "C42") (pin "1") (pinfunction "+_1") (pintype "passive"))
      (node (ref "C5") (pin "1") (pinfunction "1_1") (pintype "passive"))
      (node (ref "D2") (pin "C") (pinfunction "C_C") (pintype "passive"))
      (node (ref "D3") (pin "C") (pinfunction "C_C") (pintype "passive"))
      (node (ref "U$1") (pin "1") (pinfunction "IN_1") (pintype "bidirectional"))
      (node (ref "U$11") (pin "1") (pinfunction "IN_1") (pintype "bidirectional"))
      (node (ref "U$13") (pin "1") (pinfunction "IN_1") (pintype "bidirectional"))
      (node (ref "U$15") (pin "1") (pinfunction "IN_1") (pintype "bidirectional"))
      (node (ref "U$17") (pin "1") (pinfunction "IN_1") (pintype "bidirectional"))
      (node (ref "U$19") (pin "1") (pinfunction "IN_1") (pintype "bidirectional"))
      (node (ref "U2") (pin "1") (pinfunction "IN_1") (pintype "input"))
      (node (ref "U2") (pin "3") (pinfunction "EN_3") (pintype "input"))
    )
    (net (code "54") (name "GND") (class "Default")
      (node (ref "C1") (pin "2") (pinfunction "2_2") (pintype "passive"))
      (node (ref "C10") (pin "1") (pinfunction "1_1") (pintype "passive"))
      (node (ref "C11") (pin "1") (pinfunction "1_1") (pintype "passive"))
      (node (ref "C12") (pin "1") (pinfunction "1_1") (pintype "passive"))
      (node (ref "C13") (pin "1") (pinfunction "1_1") (pintype "passive"))
      (node (ref "C14") (pin "1") (pinfunction "1_1") (pintype "passive"))
      (node (ref "C15") (pin "1") (pinfunction "1_1") (pintype "passive"))
      (node (ref "C16") (pin "1") (pinfunction "1_1") (pintype "passive"))
      (node (ref "C17") (pin "1") (pinfunction "1_1") (pintype "passive"))
      (node (ref "C18") (pin "1") (pinfunction "1_1") (pintype "passive"))
      (node (ref "C19") (pin "1") (pinfunction "1_1") (pintype "passive"))
      (node (ref "C2") (pin "2") (pinfunction "2_2") (pintype "passive"))
      (node (ref "C20") (pin "1") (pinfunction "1_1") (pintype "passive"))
      (node (ref "C21") (pin "2") (pinfunction "2_2") (pintype "passive"))
      (node (ref "C22") (pin "2") (pinfunction "-_2") (pintype "passive"))
      (node (ref "C23") (pin "2") (pinfunction "2_2") (pintype "passive"))
      (node (ref "C24") (pin "2") (pinfunction "2_2") (pintype "passive"))
      (node (ref "C25") (pin "2") (pinfunction "-_2") (pintype "passive"))
      (node (ref "C26") (pin "2") (pinfunction "2_2") (pintype "passive"))
      (node (ref "C27") (pin "2") (pinfunction "2_2") (pintype "passive"))
      (node (ref "C28") (pin "2") (pinfunction "-_2") (pintype "passive"))
      (node (ref "C29") (pin "2") (pinfunction "2_2") (pintype "passive"))
      (node (ref "C3") (pin "1") (pinfunction "1_1") (pintype "passive"))
      (node (ref "C30") (pin "2") (pinfunction "2_2") (pintype "passive"))
      (node (ref "C31") (pin "2") (pinfunction "-_2") (pintype "passive"))
      (node (ref "C32") (pin "2") (pinfunction "2_2") (pintype "passive"))
      (node (ref "C33") (pin "2") (pinfunction "2_2") (pintype "passive"))
      (node (ref "C34") (pin "2") (pinfunction "-_2") (pintype "passive"))
      (node (ref "C35") (pin "2") (pinfunction "2_2") (pintype "passive"))
      (node (ref "C36") (pin "1") (pinfunction "1_1") (pintype "passive"))
      (node (ref "C37") (pin "1") (pinfunction "1_1") (pintype "passive"))
      (node (ref "C38") (pin "1") (pinfunction "1_1") (pintype "passive"))
      (node (ref "C39") (pin "1") (pinfunction "1_1") (pintype "passive"))
      (node (ref "C4") (pin "1") (pinfunction "1_1") (pintype "passive"))
      (node (ref "C40") (pin "2") (pinfunction "-_2") (pintype "passive"))
      (node (ref "C41") (pin "2") (pinfunction "-_2") (pintype "passive"))
      (node (ref "C42") (pin "2") (pinfunction "-_2") (pintype "passive"))
      (node (ref "C43") (pin "1") (pinfunction "1_1") (pintype "passive"))
      (node (ref "C44") (pin "1") (pinfunction "1_1") (pintype "passive"))
      (node (ref "C45") (pin "1") (pinfunction "1_1") (pintype "passive"))
      (node (ref "C46") (pin "1") (pinfunction "1_1") (pintype "passive"))
      (node (ref "C5") (pin "2") (pinfunction "2_2") (pintype "passive"))
      (node (ref "C6") (pin "1") (pinfunction "1_1") (pintype "passive"))
      (node (ref "C7") (pin "2") (pinfunction "-_2") (pintype "passive"))
      (node (ref "C8") (pin "1") (pinfunction "1_1") (pintype "passive"))
      (node (ref "C9") (pin "2") (pinfunction "2_2") (pintype "passive"))
      (node (ref "J1") (pin "PWR") (pinfunction "PWR_PWR") (pintype "bidirectional"))
      (node (ref "R1") (pin "1") (pinfunction "1_1") (pintype "passive"))
      (node (ref "R10") (pin "1") (pinfunction "1_1") (pintype "passive"))
      (node (ref "R12") (pin "1") (pinfunction "1_1") (pintype "passive"))
      (node (ref "R14") (pin "1") (pinfunction "1_1") (pintype "passive"))
      (node (ref "R16") (pin "1") (pinfunction "1_1") (pintype "passive"))
      (node (ref "R18") (pin "1") (pinfunction "1_1") (pintype "passive"))
      (node (ref "R2") (pin "1") (pinfunction "1_1") (pintype "passive"))
      (node (ref "R20") (pin "1") (pinfunction "1_1") (pintype "passive"))
      (node (ref "R22") (pin "1") (pinfunction "1_1") (pintype "passive"))
      (node (ref "R25") (pin "1") (pinfunction "1_1") (pintype "passive"))
      (node (ref "R3") (pin "1") (pinfunction "1_1") (pintype "passive"))
      (node (ref "R5") (pin "1") (pinfunction "1_1") (pintype "passive"))
      (node (ref "R6") (pin "2") (pinfunction "2_2") (pintype "passive"))
      (node (ref "R9") (pin "2") (pinfunction "2_2") (pintype "passive"))
      (node (ref "S1") (pin "1") (pinfunction "1_1") (pintype "passive"))
      (node (ref "TP3") (pin "P$1") (pinfunction "1_P$1") (pintype "bidirectional"))
      (node (ref "U$1") (pin "2") (pinfunction "GND_2") (pintype "bidirectional"))
      (node (ref "U$1") (pin "EP") (pinfunction "GND_EP") (pintype "bidirectional"))
      (node (ref "U$10") (pin "GDN2") (pinfunction "GND_GDN2") (pintype "bidirectional"))
      (node (ref "U$10") (pin "GND1") (pinfunction "GND_GND1") (pintype "bidirectional"))
      (node (ref "U$11") (pin "2") (pinfunction "GND_2") (pintype "bidirectional"))
      (node (ref "U$11") (pin "EP") (pinfunction "GND_EP") (pintype "bidirectional"))
      (node (ref "U$12") (pin "GDN2") (pinfunction "GND_GDN2") (pintype "bidirectional"))
      (node (ref "U$12") (pin "GND1") (pinfunction "GND_GND1") (pintype "bidirectional"))
      (node (ref "U$13") (pin "2") (pinfunction "GND_2") (pintype "bidirectional"))
      (node (ref "U$13") (pin "EP") (pinfunction "GND_EP") (pintype "bidirectional"))
      (node (ref "U$14") (pin "GDN2") (pinfunction "GND_GDN2") (pintype "bidirectional"))
      (node (ref "U$14") (pin "GND1") (pinfunction "GND_GND1") (pintype "bidirectional"))
      (node (ref "U$15") (pin "2") (pinfunction "GND_2") (pintype "bidirectional"))
      (node (ref "U$15") (pin "EP") (pinfunction "GND_EP") (pintype "bidirectional"))
      (node (ref "U$16") (pin "GDN2") (pinfunction "GND_GDN2") (pintype "bidirectional"))
      (node (ref "U$16") (pin "GND1") (pinfunction "GND_GND1") (pintype "bidirectional"))
      (node (ref "U$17") (pin "2") (pinfunction "GND_2") (pintype "bidirectional"))
      (node (ref "U$17") (pin "EP") (pinfunction "GND_EP") (pintype "bidirectional"))
      (node (ref "U$18") (pin "GDN2") (pinfunction "GND_GDN2") (pintype "bidirectional"))
      (node (ref "U$18") (pin "GND1") (pinfunction "GND_GND1") (pintype "bidirectional"))
      (node (ref "U$19") (pin "2") (pinfunction "GND_2") (pintype "bidirectional"))
      (node (ref "U$19") (pin "EP") (pinfunction "GND_EP") (pintype "bidirectional"))
      (node (ref "U$2") (pin "A1") (pinfunction "GND_A1") (pintype "bidirectional"))
      (node (ref "U$2") (pin "A12") (pinfunction "GND_A12") (pintype "bidirectional"))
      (node (ref "U$2") (pin "B1") (pinfunction "GND_B1") (pintype "bidirectional"))
      (node (ref "U$2") (pin "B12") (pinfunction "GND_B12") (pintype "bidirectional"))
      (node (ref "U$3") (pin "GDN2") (pinfunction "GND_GDN2") (pintype "bidirectional"))
      (node (ref "U$3") (pin "GND1") (pinfunction "GND_GND1") (pintype "bidirectional"))
      (node (ref "U$4") (pin "3") (pinfunction "GND_3") (pintype "bidirectional"))
      (node (ref "U$5") (pin "EP") (pinfunction "GND_EP") (pintype "bidirectional"))
      (node (ref "U$6") (pin "P$3") (pinfunction "GND_P$3") (pintype "power_in"))
      (node (ref "U$7") (pin "EP") (pinfunction "GND_EP") (pintype "bidirectional"))
      (node (ref "U$8") (pin "10") (pinfunction "GND_10") (pintype "bidirectional"))
      (node (ref "U$8") (pin "28") (pinfunction "GND_28") (pintype "bidirectional"))
      (node (ref "U$8") (pin "GND") (pinfunction "GND_GND") (pintype "bidirectional"))
      (node (ref "U2") (pin "2") (pinfunction "GND_2") (pintype "input"))
      (node (ref "Y1") (pin "2") (pinfunction "3_2") (pintype "passive"))
      (node (ref "Y1") (pin "4") (pinfunction "3_4") (pintype "passive"))
      (node (ref "Y2") (pin "2") (pinfunction "3_2") (pintype "passive"))
      (node (ref "Y2") (pin "4") (pinfunction "3_4") (pintype "passive"))
    )
    (net (code "55") (name "Net-(C1-Pad1)") (class "Default")
      (node (ref "C1") (pin "1") (pinfunction "1_1") (pintype "passive"))
      (node (ref "R1") (pin "2") (pinfunction "2_2") (pintype "passive"))
      (node (ref "U$3") (pin "S1B") (pinfunction "SHIELD_S1B") (pintype "bidirectional"))
      (node (ref "U$3") (pin "S1T") (pinfunction "SHIELD_S1T") (pintype "bidirectional"))
      (node (ref "U$3") (pin "S2B") (pinfunction "SHIELD_S2B") (pintype "bidirectional"))
      (node (ref "U$3") (pin "S2T") (pinfunction "SHIELD_S2T") (pintype "bidirectional"))
      (node (ref "U$3") (pin "S3B") (pinfunction "SHIELD_S3B") (pintype "bidirectional"))
      (node (ref "U$3") (pin "S3T") (pinfunction "SHIELD_S3T") (pintype "bidirectional"))
      (node (ref "U$3") (pin "S4B") (pinfunction "SHIELD_S4B") (pintype "bidirectional"))
      (node (ref "U$3") (pin "S4T") (pinfunction "SHIELD_S4T") (pintype "bidirectional"))
    )
    (net (code "56") (name "Net-(C2-Pad1)") (class "Default")
      (node (ref "C2") (pin "1") (pinfunction "1_1") (pintype "passive"))
      (node (ref "R3") (pin "2") (pinfunction "2_2") (pintype "passive"))
      (node (ref "U$2") (pin "S1B") (pinfunction "SHIELD_S1B") (pintype "bidirectional"))
      (node (ref "U$2") (pin "S1T") (pinfunction "SHIELD_S1T") (pintype "bidirectional"))
      (node (ref "U$2") (pin "S2B") (pinfunction "SHIELD_S2B") (pintype "bidirectional"))
      (node (ref "U$2") (pin "S2T") (pinfunction "SHIELD_S2T") (pintype "bidirectional"))
      (node (ref "U$2") (pin "S3B") (pinfunction "SHIELD_S3B") (pintype "bidirectional"))
      (node (ref "U$2") (pin "S3T") (pinfunction "SHIELD_S3T") (pintype "bidirectional"))
      (node (ref "U$2") (pin "S4B") (pinfunction "SHIELD_S4B") (pintype "bidirectional"))
      (node (ref "U$2") (pin "S4T") (pinfunction "SHIELD_S4T") (pintype "bidirectional"))
      (node (ref "U$2") (pin "S5B") (pinfunction "SHIELD_S5B") (pintype "bidirectional"))
      (node (ref "U$2") (pin "S5T") (pinfunction "SHIELD_S5T") (pintype "bidirectional"))
      (node (ref "U$2") (pin "S6B") (pinfunction "SHIELD_S6B") (pintype "bidirectional"))
      (node (ref "U$2") (pin "S6T") (pinfunction "SHIELD_S6T") (pintype "bidirectional"))
    )
    (net (code "57") (name "Net-(C7-+)") (class "Default")
      (node (ref "C7") (pin "1") (pinfunction "+_1") (pintype "passive"))
      (node (ref "C9") (pin "1") (pinfunction "1_1") (pintype "passive"))
      (node (ref "U$1") (pin "5") (pinfunction "OUT_5") (pintype "bidirectional"))
      (node (ref "U$3") (pin "VBUS1") (pinfunction "VBUS_VBUS1") (pintype "bidirectional"))
      (node (ref "U$3") (pin "VBUS2") (pinfunction "VBUS_VBUS2") (pintype "bidirectional"))
    )
    (net (code "58") (name "Net-(C12-Pad2)") (class "Default")
      (node (ref "C12") (pin "2") (pinfunction "2_2") (pintype "passive"))
      (node (ref "C18") (pin "2") (pinfunction "2_2") (pintype "passive"))
      (node (ref "C19") (pin "2") (pinfunction "2_2") (pintype "passive"))
      (node (ref "FB1") (pin "2") (pinfunction "2_2") (pintype "passive"))
      (node (ref "U$5") (pin "10") (pinfunction "VCCA_10") (pintype "bidirectional"))
      (node (ref "U$5") (pin "29") (pinfunction "VCCA_29") (pintype "bidirectional"))
      (node (ref "U$5") (pin "36") (pinfunction "VCCA_36") (pintype "bidirectional"))
      (node (ref "U$5") (pin "5") (pinfunction "VCCA_5") (pintype "bidirectional"))
    )
    (net (code "59") (name "Net-(C16-Pad2)") (class "Default")
      (node (ref "C16") (pin "2") (pinfunction "2_2") (pintype "passive"))
      (node (ref "C43") (pin "2") (pinfunction "2_2") (pintype "passive"))
      (node (ref "C44") (pin "2") (pinfunction "2_2") (pintype "passive"))
      (node (ref "FB2") (pin "2") (pinfunction "2_2") (pintype "passive"))
      (node (ref "U$7") (pin "10") (pinfunction "VCCA_10") (pintype "bidirectional"))
      (node (ref "U$7") (pin "29") (pinfunction "VCCA_29") (pintype "bidirectional"))
      (node (ref "U$7") (pin "36") (pinfunction "VCCA_36") (pintype "bidirectional"))
      (node (ref "U$7") (pin "5") (pinfunction "VCCA_5") (pintype "bidirectional"))
    )
    (net (code "60") (name "Net-(C21-Pad1)") (class "Default")
      (node (ref "C21") (pin "1") (pinfunction "1_1") (pintype "passive"))
      (node (ref "R12") (pin "2") (pinfunction "2_2") (pintype "passive"))
      (node (ref "U$10") (pin "S1B") (pinfunction "SHIELD_S1B") (pintype "bidirectional"))
      (node (ref "U$10") (pin "S1T") (pinfunction "SHIELD_S1T") (pintype "bidirectional"))
      (node (ref "U$10") (pin "S2B") (pinfunction "SHIELD_S2B") (pintype "bidirectional"))
      (node (ref "U$10") (pin "S2T") (pinfunction "SHIELD_S2T") (pintype "bidirectional"))
      (node (ref "U$10") (pin "S3B") (pinfunction "SHIELD_S3B") (pintype "bidirectional"))
      (node (ref "U$10") (pin "S3T") (pinfunction "SHIELD_S3T") (pintype "bidirectional"))
      (node (ref "U$10") (pin "S4B") (pinfunction "SHIELD_S4B") (pintype "bidirectional"))
      (node (ref "U$10") (pin "S4T") (pinfunction "SHIELD_S4T") (pintype "bidirectional"))
    )
    (net (code "61") (name "Net-(C22-+)") (class "Default")
      (node (ref "C22") (pin "1") (pinfunction "+_1") (pintype "passive"))
      (node (ref "C23") (pin "1") (pinfunction "1_1") (pintype "passive"))
      (node (ref "U$10") (pin "VBUS1") (pinfunction "VBUS_VBUS1") (pintype "bidirectional"))
      (node (ref "U$10") (pin "VBUS2") (pinfunction "VBUS_VBUS2") (pintype "bidirectional"))
      (node (ref "U$11") (pin "5") (pinfunction "OUT_5") (pintype "bidirectional"))
    )
    (net (code "62") (name "Net-(C24-Pad1)") (class "Default")
      (node (ref "C24") (pin "1") (pinfunction "1_1") (pintype "passive"))
      (node (ref "R14") (pin "2") (pinfunction "2_2") (pintype "passive"))
      (node (ref "U$12") (pin "S1B") (pinfunction "SHIELD_S1B") (pintype "bidirectional"))
      (node (ref "U$12") (pin "S1T") (pinfunction "SHIELD_S1T") (pintype "bidirectional"))
      (node (ref "U$12") (pin "S2B") (pinfunction "SHIELD_S2B") (pintype "bidirectional"))
      (node (ref "U$12") (pin "S2T") (pinfunction "SHIELD_S2T") (pintype "bidirectional"))
      (node (ref "U$12") (pin "S3B") (pinfunction "SHIELD_S3B") (pintype "bidirectional"))
      (node (ref "U$12") (pin "S3T") (pinfunction "SHIELD_S3T") (pintype "bidirectional"))
      (node (ref "U$12") (pin "S4B") (pinfunction "SHIELD_S4B") (pintype "bidirectional"))
      (node (ref "U$12") (pin "S4T") (pinfunction "SHIELD_S4T") (pintype "bidirectional"))
    )
    (net (code "63") (name "Net-(C25-+)") (class "Default")
      (node (ref "C25") (pin "1") (pinfunction "+_1") (pintype "passive"))
      (node (ref "C26") (pin "1") (pinfunction "1_1") (pintype "passive"))
      (node (ref "U$12") (pin "VBUS1") (pinfunction "VBUS_VBUS1") (pintype "bidirectional"))
      (node (ref "U$12") (pin "VBUS2") (pinfunction "VBUS_VBUS2") (pintype "bidirectional"))
      (node (ref "U$13") (pin "5") (pinfunction "OUT_5") (pintype "bidirectional"))
    )
    (net (code "64") (name "Net-(C27-Pad1)") (class "Default")
      (node (ref "C27") (pin "1") (pinfunction "1_1") (pintype "passive"))
      (node (ref "R16") (pin "2") (pinfunction "2_2") (pintype "passive"))
      (node (ref "U$14") (pin "S1B") (pinfunction "SHIELD_S1B") (pintype "bidirectional"))
      (node (ref "U$14") (pin "S1T") (pinfunction "SHIELD_S1T") (pintype "bidirectional"))
      (node (ref "U$14") (pin "S2B") (pinfunction "SHIELD_S2B") (pintype "bidirectional"))
      (node (ref "U$14") (pin "S2T") (pinfunction "SHIELD_S2T") (pintype "bidirectional"))
      (node (ref "U$14") (pin "S3B") (pinfunction "SHIELD_S3B") (pintype "bidirectional"))
      (node (ref "U$14") (pin "S3T") (pinfunction "SHIELD_S3T") (pintype "bidirectional"))
      (node (ref "U$14") (pin "S4B") (pinfunction "SHIELD_S4B") (pintype "bidirectional"))
      (node (ref "U$14") (pin "S4T") (pinfunction "SHIELD_S4T") (pintype "bidirectional"))
    )
    (net (code "65") (name "Net-(C28-+)") (class "Default")
      (node (ref "C28") (pin "1") (pinfunction "+_1") (pintype "passive"))
      (node (ref "C29") (pin "1") (pinfunction "1_1") (pintype "passive"))
      (node (ref "U$14") (pin "VBUS1") (pinfunction "VBUS_VBUS1") (pintype "bidirectional"))
      (node (ref "U$14") (pin "VBUS2") (pinfunction "VBUS_VBUS2") (pintype "bidirectional"))
      (node (ref "U$15") (pin "5") (pinfunction "OUT_5") (pintype "bidirectional"))
    )
    (net (code "66") (name "Net-(C30-Pad1)") (class "Default")
      (node (ref "C30") (pin "1") (pinfunction "1_1") (pintype "passive"))
      (node (ref "R18") (pin "2") (pinfunction "2_2") (pintype "passive"))
      (node (ref "U$16") (pin "S1B") (pinfunction "SHIELD_S1B") (pintype "bidirectional"))
      (node (ref "U$16") (pin "S1T") (pinfunction "SHIELD_S1T") (pintype "bidirectional"))
      (node (ref "U$16") (pin "S2B") (pinfunction "SHIELD_S2B") (pintype "bidirectional"))
      (node (ref "U$16") (pin "S2T") (pinfunction "SHIELD_S2T") (pintype "bidirectional"))
      (node (ref "U$16") (pin "S3B") (pinfunction "SHIELD_S3B") (pintype "bidirectional"))
      (node (ref "U$16") (pin "S3T") (pinfunction "SHIELD_S3T") (pintype "bidirectional"))
      (node (ref "U$16") (pin "S4B") (pinfunction "SHIELD_S4B") (pintype "bidirectional"))
      (node (ref "U$16") (pin "S4T") (pinfunction "SHIELD_S4T") (pintype "bidirectional"))
    )
    (net (code "67") (name "Net-(C31-+)") (class "Default")
      (node (ref "C31") (pin "1") (pinfunction "+_1") (pintype "passive"))
      (node (ref "C32") (pin "1") (pinfunction "1_1") (pintype "passive"))
      (node (ref "U$16") (pin "VBUS1") (pinfunction "VBUS_VBUS1") (pintype "bidirectional"))
      (node (ref "U$16") (pin "VBUS2") (pinfunction "VBUS_VBUS2") (pintype "bidirectional"))
      (node (ref "U$17") (pin "5") (pinfunction "OUT_5") (pintype "bidirectional"))
    )
    (net (code "68") (name "Net-(C33-Pad1)") (class "Default")
      (node (ref "C33") (pin "1") (pinfunction "1_1") (pintype "passive"))
      (node (ref "R20") (pin "2") (pinfunction "2_2") (pintype "passive"))
      (node (ref "U$18") (pin "S1B") (pinfunction "SHIELD_S1B") (pintype "bidirectional"))
      (node (ref "U$18") (pin "S1T") (pinfunction "SHIELD_S1T") (pintype "bidirectional"))
      (node (ref "U$18") (pin "S2B") (pinfunction "SHIELD_S2B") (pintype "bidirectional"))
      (node (ref "U$18") (pin "S2T") (pinfunction "SHIELD_S2T") (pintype "bidirectional"))
      (node (ref "U$18") (pin "S3B") (pinfunction "SHIELD_S3B") (pintype "bidirectional"))
      (node (ref "U$18") (pin "S3T") (pinfunction "SHIELD_S3T") (pintype "bidirectional"))
      (node (ref "U$18") (pin "S4B") (pinfunction "SHIELD_S4B") (pintype "bidirectional"))
      (node (ref "U$18") (pin "S4T") (pinfunction "SHIELD_S4T") (pintype "bidirectional"))
    )
    (net (code "69") (name "Net-(C34-+)") (class "Default")
      (node (ref "C34") (pin "1") (pinfunction "+_1") (pintype "passive"))
      (node (ref "C35") (pin "1") (pinfunction "1_1") (pintype "passive"))
      (node (ref "U$18") (pin "VBUS1") (pinfunction "VBUS_VBUS1") (pintype "bidirectional"))
      (node (ref "U$18") (pin "VBUS2") (pinfunction "VBUS_VBUS2") (pintype "bidirectional"))
      (node (ref "U$19") (pin "5") (pinfunction "OUT_5") (pintype "bidirectional"))
    )
    (net (code "70") (name "Net-(C40-+)") (class "Default")
      (node (ref "C40") (pin "1") (pinfunction "+_1") (pintype "passive"))
      (node (ref "J1") (pin "GND") (pinfunction "GND_GND") (pintype "bidirectional"))
      (node (ref "J1") (pin "GNDBREAK") (pinfunction "GNDBREAK_GNDBREAK") (pintype "bidirectional"))
      (node (ref "R8") (pin "1") (pinfunction "1_1") (pintype "passive"))
      (node (ref "U$6") (pin "P$1") (pinfunction "I+_1_P$1") (pintype "bidirectional"))
    )
    (net (code "71") (name "Net-(U$5-CRFILT)") (class "Default")
      (node (ref "C10") (pin "2") (pinfunction "2_2") (pintype "passive"))
      (node (ref "U$5") (pin "14") (pinfunction "CRFILT_14") (pintype "bidirectional"))
    )
    (net (code "72") (name "Net-(U$5-HS_IND{slash}CFG_SEL1)") (class "Default")
      (node (ref "R22") (pin "2") (pinfunction "2_2") (pintype "passive"))
      (node (ref "U$5") (pin "25") (pinfunction "HS_IND/CFG_SEL1_25") (pintype "bidirectional"))
    )
    (net (code "73") (name "Net-(U$5-PLLFILT)") (class "Default")
      (node (ref "C11") (pin "2") (pinfunction "2_2") (pintype "passive"))
      (node (ref "U$5") (pin "34") (pinfunction "PLLFILT_34") (pintype "bidirectional"))
    )
    (net (code "74") (name "Net-(U$5-RBIAS)") (class "Default")
      (node (ref "R2") (pin "2") (pinfunction "2_2") (pintype "passive"))
      (node (ref "U$5") (pin "35") (pinfunction "RBIAS_35") (pintype "bidirectional"))
    )
    (net (code "75") (name "Net-(U$5-XTALIN{slash}CLKIN)") (class "Default")
      (node (ref "C38") (pin "2") (pinfunction "2_2") (pintype "passive"))
      (node (ref "U$5") (pin "33") (pinfunction "XTALIN/CLKIN_33") (pintype "bidirectional"))
      (node (ref "Y1") (pin "1") (pinfunction "1_1") (pintype "passive"))
    )
    (net (code "76") (name "Net-(U$5-XTALOUT)") (class "Default")
      (node (ref "C39") (pin "2") (pinfunction "2_2") (pintype "passive"))
      (node (ref "U$5") (pin "32") (pinfunction "XTALOUT_32") (pintype "bidirectional"))
      (node (ref "Y1") (pin "3") (pinfunction "2_3") (pintype "passive"))
    )
    (net (code "77") (name "Net-(U$6-I-_1)") (class "Default")
      (node (ref "D3") (pin "A") (pinfunction "A_A") (pintype "passive"))
      (node (ref "U$6") (pin "P$2") (pinfunction "I-_1_P$2") (pintype "bidirectional"))
    )
    (net (code "78") (name "Net-(U$7-CRFILT)") (class "Default")
      (node (ref "C14") (pin "2") (pinfunction "2_2") (pintype "passive"))
      (node (ref "U$7") (pin "14") (pinfunction "CRFILT_14") (pintype "bidirectional"))
    )
    (net (code "79") (name "Net-(U$7-HS_IND{slash}CFG_SEL1)") (class "Default")
      (node (ref "R25") (pin "2") (pinfunction "2_2") (pintype "passive"))
      (node (ref "U$7") (pin "25") (pinfunction "HS_IND/CFG_SEL1_25") (pintype "bidirectional"))
    )
    (net (code "80") (name "Net-(U$7-PLLFILT)") (class "Default")
      (node (ref "C15") (pin "2") (pinfunction "2_2") (pintype "passive"))
      (node (ref "U$7") (pin "34") (pinfunction "PLLFILT_34") (pintype "bidirectional"))
    )
    (net (code "81") (name "Net-(U$7-RBIAS)") (class "Default")
      (node (ref "R10") (pin "2") (pinfunction "2_2") (pintype "passive"))
      (node (ref "U$7") (pin "35") (pinfunction "RBIAS_35") (pintype "bidirectional"))
    )
    (net (code "82") (name "Net-(U$7-XTALIN{slash}CLKIN)") (class "Default")
      (node (ref "C8") (pin "2") (pinfunction "2_2") (pintype "passive"))
      (node (ref "U$7") (pin "33") (pinfunction "XTALIN/CLKIN_33") (pintype "bidirectional"))
      (node (ref "Y2") (pin "1") (pinfunction "1_1") (pintype "passive"))
    )
    (net (code "83") (name "Net-(U$7-XTALOUT)") (class "Default")
      (node (ref "C37") (pin "2") (pinfunction "2_2") (pintype "passive"))
      (node (ref "U$7") (pin "32") (pinfunction "XTALOUT_32") (pintype "bidirectional"))
      (node (ref "Y2") (pin "3") (pinfunction "2_3") (pintype "passive"))
    )
    (net (code "84") (name "Net-(U$8-VDDCORE)") (class "Default")
      (node (ref "C36") (pin "2") (pinfunction "2_2") (pintype "passive"))
      (node (ref "U$8") (pin "29") (pinfunction "VDDCORE_29") (pintype "bidirectional"))
    )
    (net (code "85") (name "unconnected-(U$2-B+-PadA11)") (class "Default")
      (node (ref "U$2") (pin "A11") (pinfunction "B+_A11") (pintype "bidirectional"))
    )
    (net (code "86") (name "unconnected-(U$2-B--PadA10)") (class "Default")
      (node (ref "U$2") (pin "A10") (pinfunction "B-_A10") (pintype "bidirectional"))
    )
    (net (code "87") (name "unconnected-(U$2-D+-PadB2)") (class "Default")
      (node (ref "U$2") (pin "B2") (pinfunction "D+_B2") (pintype "bidirectional"))
    )
    (net (code "88") (name "unconnected-(U$2-D--PadB3)") (class "Default")
      (node (ref "U$2") (pin "B3") (pinfunction "D-_B3") (pintype "bidirectional"))
    )
    (net (code "89") (name "unconnected-(U$3-PadSBU1)") (class "Default")
      (node (ref "U$3") (pin "SBU1") (pinfunction "SBU1_SBU1") (pintype "bidirectional"))
    )
    (net (code "90") (name "unconnected-(U$3-PadSBU2)") (class "Default")
      (node (ref "U$3") (pin "SBU2") (pinfunction "SBU2_SBU2") (pintype "bidirectional"))
    )
    (net (code "91") (name "unconnected-(U$5-OCS1-Pad13)") (class "Default")
      (node (ref "U$5") (pin "13") (pinfunction "OCS1_13") (pintype "bidirectional"))
    )
    (net (code "92") (name "unconnected-(U$5-OCS2-Pad17)") (class "Default")
      (node (ref "U$5") (pin "17") (pinfunction "OCS2_17") (pintype "bidirectional"))
    )
    (net (code "93") (name "unconnected-(U$5-OCS3-Pad19)") (class "Default")
      (node (ref "U$5") (pin "19") (pinfunction "OCS3_19") (pintype "bidirectional"))
    )
    (net (code "94") (name "unconnected-(U$5-OCS4-Pad21)") (class "Default")
      (node (ref "U$5") (pin "21") (pinfunction "OCS4_21") (pintype "bidirectional"))
    )
    (net (code "95") (name "unconnected-(U$5-PWR{slash}BC1-Pad12)") (class "Default")
      (node (ref "U$5") (pin "12") (pinfunction "PWR/BC1_12") (pintype "bidirectional"))
    )
    (net (code "96") (name "unconnected-(U$5-PWR{slash}BC2-Pad16)") (class "Default")
      (node (ref "U$5") (pin "16") (pinfunction "PWR/BC2_16") (pintype "bidirectional"))
    )
    (net (code "97") (name "unconnected-(U$5-PWR{slash}BC3-Pad18)") (class "Default")
      (node (ref "U$5") (pin "18") (pinfunction "PWR/BC3_18") (pintype "bidirectional"))
    )
    (net (code "98") (name "unconnected-(U$5-PWR{slash}BC4-Pad20)") (class "Default")
      (node (ref "U$5") (pin "20") (pinfunction "PWR/BC4_20") (pintype "bidirectional"))
    )
    (net (code "99") (name "unconnected-(U$6-FAULT-PadP$4)") (class "Default")
      (node (ref "U$6") (pin "P$4") (pinfunction "FAULT_P$4") (pintype "bidirectional"))
    )
    (net (code "100") (name "unconnected-(U$7-OCS1-Pad13)") (class "Default")
      (node (ref "U$7") (pin "13") (pinfunction "OCS1_13") (pintype "bidirectional"))
    )
    (net (code "101") (name "unconnected-(U$7-OCS2-Pad17)") (class "Default")
      (node (ref "U$7") (pin "17") (pinfunction "OCS2_17") (pintype "bidirectional"))
    )
    (net (code "102") (name "unconnected-(U$7-OCS3-Pad19)") (class "Default")
      (node (ref "U$7") (pin "19") (pinfunction "OCS3_19") (pintype "bidirectional"))
    )
    (net (code "103") (name "unconnected-(U$7-OCS4-Pad21)") (class "Default")
      (node (ref "U$7") (pin "21") (pinfunction "OCS4_21") (pintype "bidirectional"))
    )
    (net (code "104") (name "unconnected-(U$7-PWR{slash}BC1-Pad12)") (class "Default")
      (node (ref "U$7") (pin "12") (pinfunction "PWR/BC1_12") (pintype "bidirectional"))
    )
    (net (code "105") (name "unconnected-(U$7-PWR{slash}BC2-Pad16)") (class "Default")
      (node (ref "U$7") (pin "16") (pinfunction "PWR/BC2_16") (pintype "bidirectional"))
    )
    (net (code "106") (name "unconnected-(U$7-PWR{slash}BC3-Pad18)") (class "Default")
      (node (ref "U$7") (pin "18") (pinfunction "PWR/BC3_18") (pintype "bidirectional"))
    )
    (net (code "107") (name "unconnected-(U$7-PWR{slash}BC4-Pad20)") (class "Default")
      (node (ref "U$7") (pin "20") (pinfunction "PWR/BC4_20") (pintype "bidirectional"))
    )
    (net (code "108") (name "unconnected-(U$8-PA00-Pad1)") (class "Default")
      (node (ref "U$8") (pin "1") (pinfunction "PA00_1") (pintype "bidirectional"))
    )
    (net (code "109") (name "unconnected-(U$8-PA01-Pad2)") (class "Default")
      (node (ref "U$8") (pin "2") (pinfunction "PA01_2") (pintype "bidirectional"))
    )
    (net (code "110") (name "unconnected-(U$8-PA02-Pad3)") (class "Default")
      (node (ref "U$8") (pin "3") (pinfunction "PA02_3") (pintype "bidirectional"))
    )
    (net (code "111") (name "unconnected-(U$8-PA03-Pad4)") (class "Default")
      (node (ref "U$8") (pin "4") (pinfunction "PA03_4") (pintype "bidirectional"))
    )
    (net (code "112") (name "unconnected-(U$8-PA04-Pad5)") (class "Default")
      (node (ref "U$8") (pin "5") (pinfunction "PA04_5") (pintype "bidirectional"))
    )
    (net (code "113") (name "unconnected-(U$8-PA05-Pad6)") (class "Default")
      (node (ref "U$8") (pin "6") (pinfunction "PA05_6") (pintype "bidirectional"))
    )
    (net (code "114") (name "unconnected-(U$8-PA06-Pad7)") (class "Default")
      (node (ref "U$8") (pin "7") (pinfunction "PA06_7") (pintype "bidirectional"))
    )
    (net (code "115") (name "unconnected-(U$8-PA07-Pad8)") (class "Default")
      (node (ref "U$8") (pin "8") (pinfunction "PA07_8") (pintype "bidirectional"))
    )
    (net (code "116") (name "unconnected-(U$8-PA08-Pad11)") (class "Default")
      (node (ref "U$8") (pin "11") (pinfunction "PA08_11") (pintype "bidirectional"))
    )
    (net (code "117") (name "unconnected-(U$8-PA09-Pad12)") (class "Default")
      (node (ref "U$8") (pin "12") (pinfunction "PA09_12") (pintype "bidirectional"))
    )
    (net (code "118") (name "unconnected-(U$8-PA10-Pad13)") (class "Default")
      (node (ref "U$8") (pin "13") (pinfunction "PA10_13") (pintype "bidirectional"))
    )
    (net (code "119") (name "unconnected-(U$8-PA11-Pad14)") (class "Default")
      (node (ref "U$8") (pin "14") (pinfunction "PA11_14") (pintype "bidirectional"))
    )
    (net (code "120") (name "unconnected-(U$8-PA14-Pad15)") (class "Default")
      (node (ref "U$8") (pin "15") (pinfunction "PA14_15") (pintype "bidirectional"))
    )
    (net (code "121") (name "unconnected-(U$8-PA15-Pad16)") (class "Default")
      (node (ref "U$8") (pin "16") (pinfunction "PA15_16") (pintype "bidirectional"))
    )
    (net (code "122") (name "unconnected-(U$8-PA16-Pad17)") (class "Default")
      (node (ref "U$8") (pin "17") (pinfunction "PA16_17") (pintype "bidirectional"))
    )
    (net (code "123") (name "unconnected-(U$8-PA17-Pad18)") (class "Default")
      (node (ref "U$8") (pin "18") (pinfunction "PA17_18") (pintype "bidirectional"))
    )
    (net (code "124") (name "unconnected-(U$8-PA18-Pad19)") (class "Default")
      (node (ref "U$8") (pin "19") (pinfunction "PA18_19") (pintype "bidirectional"))
    )
    (net (code "125") (name "unconnected-(U$8-PA19-Pad20)") (class "Default")
      (node (ref "U$8") (pin "20") (pinfunction "PA19_20") (pintype "bidirectional"))
    )
    (net (code "126") (name "unconnected-(U$8-PA22-Pad21)") (class "Default")
      (node (ref "U$8") (pin "21") (pinfunction "PA22_21") (pintype "bidirectional"))
    )
    (net (code "127") (name "unconnected-(U$8-PA23-Pad22)") (class "Default")
      (node (ref "U$8") (pin "22") (pinfunction "PA23_22") (pintype "bidirectional"))
    )
    (net (code "128") (name "unconnected-(U$8-PA27-Pad25)") (class "Default")
      (node (ref "U$8") (pin "25") (pinfunction "PA27_25") (pintype "bidirectional"))
    )
    (net (code "129") (name "unconnected-(U$8-PA28-Pad27)") (class "Default")
      (node (ref "U$8") (pin "27") (pinfunction "PA28_27") (pintype "bidirectional"))
    )
    (net (code "130") (name "unconnected-(U$10-PadSBU1)") (class "Default")
      (node (ref "U$10") (pin "SBU1") (pinfunction "SBU1_SBU1") (pintype "bidirectional"))
    )
    (net (code "131") (name "unconnected-(U$10-PadSBU2)") (class "Default")
      (node (ref "U$10") (pin "SBU2") (pinfunction "SBU2_SBU2") (pintype "bidirectional"))
    )
    (net (code "132") (name "unconnected-(U$12-PadSBU1)") (class "Default")
      (node (ref "U$12") (pin "SBU1") (pinfunction "SBU1_SBU1") (pintype "bidirectional"))
    )
    (net (code "133") (name "unconnected-(U$12-PadSBU2)") (class "Default")
      (node (ref "U$12") (pin "SBU2") (pinfunction "SBU2_SBU2") (pintype "bidirectional"))
    )
    (net (code "134") (name "unconnected-(U$14-PadSBU1)") (class "Default")
      (node (ref "U$14") (pin "SBU1") (pinfunction "SBU1_SBU1") (pintype "bidirectional"))
    )
    (net (code "135") (name "unconnected-(U$14-PadSBU2)") (class "Default")
      (node (ref "U$14") (pin "SBU2") (pinfunction "SBU2_SBU2") (pintype "bidirectional"))
    )
    (net (code "136") (name "unconnected-(U$16-PadSBU1)") (class "Default")
      (node (ref "U$16") (pin "SBU1") (pinfunction "SBU1_SBU1") (pintype "bidirectional"))
    )
    (net (code "137") (name "unconnected-(U$16-PadSBU2)") (class "Default")
      (node (ref "U$16") (pin "SBU2") (pinfunction "SBU2_SBU2") (pintype "bidirectional"))
    )
    (net (code "138") (name "unconnected-(U$18-PadSBU1)") (class "Default")
      (node (ref "U$18") (pin "SBU1") (pinfunction "SBU1_SBU1") (pintype "bidirectional"))
    )
    (net (code "139") (name "unconnected-(U$18-PadSBU2)") (class "Default")
      (node (ref "U$18") (pin "SBU2") (pinfunction "SBU2_SBU2") (pintype "bidirectional"))
    )
    (net (code "140") (name "unconnected-(U2-NC-Pad4)") (class "Default")
      (node (ref "U2") (pin "4") (pinfunction "NC_4") (pintype "no_connect"))
    )
  )
)
